# IFscaner.net
KiCad netlist of a schematic drawn in Altium Designer
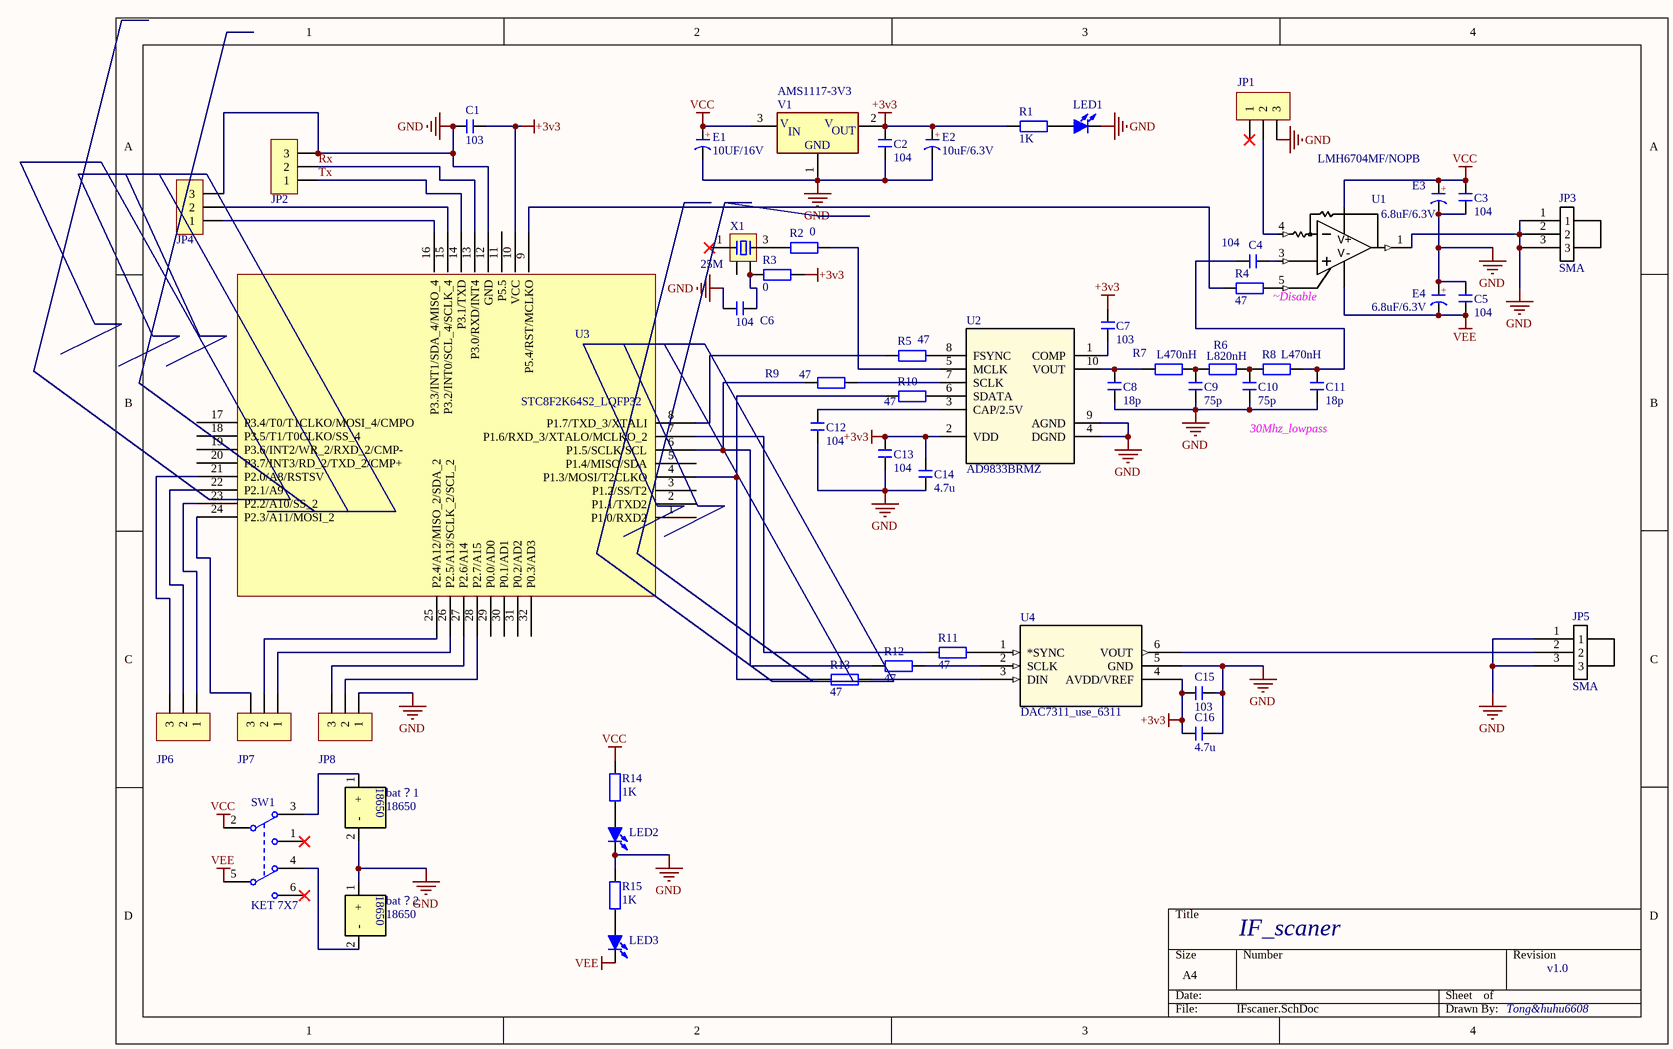
[diagram p0: IFscaner.SchDoc]

(export (version "E")
  (design (tool "Eeschema 10.0.6"))
  (components
    (comp (ref "bat？1") (value "18650") (footprint "18650base") (libsource (lib "InBoard") (part "18650")))
    (comp (ref "bat？2") (value "18650") (footprint "18650base") (libsource (lib "InBoard") (part "18650")))
    (comp (ref "C1")
      (value "103")
      (footprint "C 0603")
      (description "无极性贴片电容")
      (fields (field (name "版权归属") "源创客"))
      (libsource (lib "InBoard") (part "C"))
    )
    (comp (ref "C2")
      (value "104")
      (footprint "C 0603")
      (description "无极性贴片电容")
      (fields (field (name "版权归属") "源创客"))
      (libsource (lib "InBoard") (part "C"))
    )
    (comp (ref "C3")
      (value "104")
      (footprint "C 0603")
      (description "无极性贴片电容")
      (fields (field (name "版权归属") "源创客"))
      (libsource (lib "InBoard") (part "C"))
    )
    (comp (ref "C4")
      (value "104")
      (footprint "C 0603")
      (description "无极性贴片电容")
      (fields (field (name "版权归属") "源创客"))
      (libsource (lib "InBoard") (part "C"))
    )
    (comp (ref "C5")
      (value "104")
      (footprint "C 0603")
      (description "无极性贴片电容")
      (fields (field (name "版权归属") "源创客"))
      (libsource (lib "InBoard") (part "C"))
    )
    (comp (ref "C6")
      (value "104")
      (footprint "C 0603")
      (description "无极性贴片电容")
      (fields (field (name "版权归属") "源创客"))
      (libsource (lib "InBoard") (part "C"))
    )
    (comp (ref "C7")
      (value "103")
      (footprint "C 0603")
      (description "无极性贴片电容")
      (fields (field (name "版权归属") "源创客"))
      (libsource (lib "InBoard") (part "C"))
    )
    (comp (ref "C8")
      (value "18p")
      (footprint "C 0603")
      (description "无极性贴片电容")
      (fields (field (name "版权归属") "源创客"))
      (libsource (lib "InBoard") (part "C"))
    )
    (comp (ref "C9")
      (value "75p")
      (footprint "C 0603")
      (description "无极性贴片电容")
      (fields (field (name "版权归属") "源创客"))
      (libsource (lib "InBoard") (part "C"))
    )
    (comp (ref "C10")
      (value "75p")
      (footprint "C 0603")
      (description "无极性贴片电容")
      (fields (field (name "版权归属") "源创客"))
      (libsource (lib "InBoard") (part "C"))
    )
    (comp (ref "C11")
      (value "18p")
      (footprint "C 0603")
      (description "无极性贴片电容")
      (fields (field (name "版权归属") "源创客"))
      (libsource (lib "InBoard") (part "C"))
    )
    (comp (ref "C12")
      (value "104")
      (footprint "C 0603")
      (description "无极性贴片电容")
      (fields (field (name "版权归属") "源创客"))
      (libsource (lib "InBoard") (part "C"))
    )
    (comp (ref "C13")
      (value "104")
      (footprint "C 0603")
      (description "无极性贴片电容")
      (fields (field (name "版权归属") "源创客"))
      (libsource (lib "InBoard") (part "C"))
    )
    (comp (ref "C14")
      (value "4.7u")
      (footprint "C 0603")
      (description "无极性贴片电容")
      (fields (field (name "版权归属") "源创客"))
      (libsource (lib "InBoard") (part "C"))
    )
    (comp (ref "C15")
      (value "103")
      (footprint "C 0603")
      (description "无极性贴片电容")
      (fields (field (name "版权归属") "源创客"))
      (libsource (lib "InBoard") (part "C"))
    )
    (comp (ref "C16")
      (value "4.7u")
      (footprint "C 0603")
      (description "无极性贴片电容")
      (fields (field (name "版权归属") "源创客"))
      (libsource (lib "InBoard") (part "C"))
    )
    (comp (ref "E1")
      (value "10UF/16V")
      (footprint "CAP 5.0*10*20")
      (description "直插电解电容")
      (fields (field (name "版权归属") "源创客"))
      (libsource (lib "InBoard") (part "C-CAP"))
    )
    (comp (ref "E2")
      (value "10uF/6.3V")
      (footprint "CD B(3528)")
      (description "贴片钽电容")
      (fields (field (name "版权归属") "源创客"))
      (libsource (lib "InBoard") (part "C-CD"))
    )
    (comp (ref "E3")
      (value "6.8uF/6.3V")
      (footprint "CD B(3528)")
      (description "贴片钽电容")
      (fields (field (name "版权归属") "源创客"))
      (libsource (lib "InBoard") (part "C-CD"))
    )
    (comp (ref "E4")
      (value "6.8uF/6.3V")
      (footprint "CD B(3528)")
      (description "贴片钽电容")
      (fields (field (name "版权归属") "源创客"))
      (libsource (lib "InBoard") (part "C-CD"))
    )
    (comp (ref "JP1")
      (value "HDR-1X3")
      (footprint "HDR-1X3")
      (description "3P接插件")
      (fields (field (name "版权归属") "源创客"))
      (libsource (lib "") (part "Header 3_1"))
    )
    (comp (ref "JP2")
      (value "HDR-1X3")
      (footprint "HDR-1X3")
      (description "3P接插件")
      (fields (field (name "版权归属") "源创客"))
      (libsource (lib "") (part "Header 3_2"))
    )
    (comp (ref "JP3") (value "SMA") (footprint "SMA_khd") (libsource (lib "InBoard") (part "sma")))
    (comp (ref "JP4")
      (value "HDR-1X3")
      (footprint "HDR-1X3")
      (description "3P接插件")
      (fields (field (name "版权归属") "源创客"))
      (libsource (lib "") (part "Header 3_2"))
    )
    (comp (ref "JP5") (value "SMA") (footprint "SMA_khd") (libsource (lib "InBoard") (part "sma")))
    (comp (ref "JP6")
      (value "HDR-1X3")
      (footprint "HDR-1X3")
      (description "3P接插件")
      (fields (field (name "版权归属") "源创客"))
      (libsource (lib "InBoard") (part "Header 3"))
    )
    (comp (ref "JP7")
      (value "HDR-1X3")
      (footprint "HDR-1X3")
      (description "3P接插件")
      (fields (field (name "版权归属") "源创客"))
      (libsource (lib "InBoard") (part "Header 3"))
    )
    (comp (ref "JP8")
      (value "HDR-1X3")
      (footprint "HDR-1X3")
      (description "3P接插件")
      (fields (field (name "版权归属") "源创客"))
      (libsource (lib "InBoard") (part "Header 3"))
    )
    (comp (ref "LED1")
      (value "~")
      (footprint "LED 0603B")
      (description "贴片LED")
      (libsource (lib "InBoard") (part "LED-SMD"))
    )
    (comp (ref "LED2")
      (value "~")
      (footprint "LED 0603B")
      (description "贴片LED")
      (libsource (lib "InBoard") (part "LED-SMD"))
    )
    (comp (ref "LED3")
      (value "~")
      (footprint "LED 0603B")
      (description "贴片LED")
      (libsource (lib "InBoard") (part "LED-SMD"))
    )
    (comp (ref "R1")
      (value "1K")
      (footprint "R 0603")
      (description "贴片电阻")
      (fields (field (name "版权归属") "源创客"))
      (libsource (lib "InBoard") (part "R"))
    )
    (comp (ref "R2")
      (value "0")
      (footprint "R 0603")
      (description "贴片电阻")
      (fields (field (name "版权归属") "源创客"))
      (libsource (lib "InBoard") (part "R"))
    )
    (comp (ref "R3")
      (value "0")
      (footprint "R 0603")
      (description "贴片电阻")
      (fields (field (name "版权归属") "源创客"))
      (libsource (lib "InBoard") (part "R"))
    )
    (comp (ref "R4")
      (value "47")
      (footprint "R 0603")
      (description "贴片电阻")
      (fields (field (name "版权归属") "源创客"))
      (libsource (lib "InBoard") (part "R"))
    )
    (comp (ref "R5")
      (value "47")
      (footprint "R 0603")
      (description "贴片电阻")
      (fields (field (name "版权归属") "源创客"))
      (libsource (lib "InBoard") (part "R"))
    )
    (comp (ref "R6")
      (value "L820nH")
      (footprint "R 0603")
      (description "贴片电阻")
      (fields (field (name "版权归属") "源创客"))
      (libsource (lib "InBoard") (part "R"))
    )
    (comp (ref "R7")
      (value "L470nH")
      (footprint "R 0603")
      (description "贴片电阻")
      (fields (field (name "版权归属") "源创客"))
      (libsource (lib "InBoard") (part "R"))
    )
    (comp (ref "R8")
      (value "L470nH")
      (footprint "R 0603")
      (description "贴片电阻")
      (fields (field (name "版权归属") "源创客"))
      (libsource (lib "InBoard") (part "R"))
    )
    (comp (ref "R9")
      (value "47")
      (footprint "R 0603")
      (description "贴片电阻")
      (fields (field (name "版权归属") "源创客"))
      (libsource (lib "InBoard") (part "R"))
    )
    (comp (ref "R10")
      (value "47")
      (footprint "R 0603")
      (description "贴片电阻")
      (fields (field (name "版权归属") "源创客"))
      (libsource (lib "InBoard") (part "R"))
    )
    (comp (ref "R11")
      (value "47")
      (footprint "R 0603")
      (description "贴片电阻")
      (fields (field (name "版权归属") "源创客"))
      (libsource (lib "InBoard") (part "R"))
    )
    (comp (ref "R12")
      (value "47")
      (footprint "R 0603")
      (description "贴片电阻")
      (fields (field (name "版权归属") "源创客"))
      (libsource (lib "InBoard") (part "R"))
    )
    (comp (ref "R13")
      (value "47")
      (footprint "R 0603")
      (description "贴片电阻")
      (fields (field (name "版权归属") "源创客"))
      (libsource (lib "InBoard") (part "R"))
    )
    (comp (ref "R14")
      (value "1K")
      (footprint "R 0603")
      (description "贴片电阻")
      (fields (field (name "版权归属") "源创客"))
      (libsource (lib "InBoard") (part "R"))
    )
    (comp (ref "R15")
      (value "1K")
      (footprint "R 0603")
      (description "贴片电阻")
      (fields (field (name "版权归属") "源创客"))
      (libsource (lib "InBoard") (part "R"))
    )
    (comp (ref "SW1")
      (value "KET 7X7")
      (footprint "KFT DIP-7X7")
      (description "7*7自锁开关")
      (fields (field (name "版权归属") "源创客"))
      (libsource (lib "InBoard") (part "KET 7X7"))
    )
    (comp (ref "U1")
      (value "LMH6704MF/NOPB")
      (footprint "SOT23-6L")
      (fields
        (field (name "PARTNUMBER") "LMH6704MF")
        (field (name "MANUFACTURER") "NationalSemiconductor")
        (field (name "COPYRIGHT") "Copyright (C) 2018 Accelerated Designs. All rights reserved")
        (field (name "PUBLISHER") "NationalSemiconductor")
      )
      (libsource (lib "InBoard") (part "LMH6704MF/NOPB"))
    )
    (comp (ref "U2")
      (value "AD9833BRMZ")
      (footprint "RM_10")
      (description "Imported")
      (libsource (lib "InBoard") (part "AD9833BRMZ"))
    )
    (comp (ref "U3")
      (value "STC8F2K64S2_LQFP32")
      (footprint "LQFP32")
      (libsource (lib "InBoard") (part "STC8F2K32S2_LQFP32"))
    )
    (comp (ref "U4")
      (value "DAC7311_use_6311")
      (footprint "DCK6")
      (description "Imported")
      (fields
        (field (name "MANUFACTURER") "Texas Instruments")
        (field (name "GENERIC_PART_NUMBER") "DAC7311")
      )
      (libsource (lib "InBoard") (part "DAC7311_DCK_6"))
    )
    (comp (ref "V1")
      (value "AMS1117-3V3")
      (footprint "SOT223")
      (description "三端稳压芯片")
      (libsource (lib "InBoard") (part "AMS1117"))
    )
    (comp (ref "X1")
      (value "25M")
      (footprint "XTAL-3225")
      (description "4脚晶振")
      (libsource (lib "InBoard") (part "XTAL-4"))
    )
  )
  (nets
    (net (code "1") (name "+3v3") (class "Default")
      (node (ref "C1") (pin "2") (pinfunction "2_2") (pintype "passive"))
      (node (ref "C13") (pin "1") (pinfunction "1_1") (pintype "passive"))
      (node (ref "C14") (pin "1") (pinfunction "1_1") (pintype "passive"))
      (node (ref "C15") (pin "2") (pinfunction "2_2") (pintype "passive"))
      (node (ref "C16") (pin "2") (pinfunction "2_2") (pintype "passive"))
      (node (ref "C2") (pin "2") (pinfunction "2_2") (pintype "passive"))
      (node (ref "C7") (pin "2") (pinfunction "2_2") (pintype "passive"))
      (node (ref "E2") (pin "1") (pinfunction "A_1") (pintype "passive"))
      (node (ref "R1") (pin "2") (pinfunction "2_2") (pintype "passive"))
      (node (ref "R3") (pin "2") (pinfunction "2_2") (pintype "passive"))
      (node (ref "U2") (pin "2") (pinfunction "VDD_2") (pintype "power_in"))
      (node (ref "U3") (pin "10") (pinfunction "VCC_10") (pintype "passive"))
      (node (ref "U4") (pin "4") (pinfunction "AVDD/VREF_4") (pintype "power_in"))
      (node (ref "V1") (pin "2") (pinfunction "VOUT_2") (pintype "passive"))
    )
    (net (code "2") (name "/Rx") (class "Default")
      (node (ref "JP2") (pin "2") (pinfunction "2_2") (pintype "passive"))
      (node (ref "U3") (pin "13") (pinfunction "P3.0/RXD/INT4_13") (pintype "passive"))
    )
    (net (code "3") (name "/Tx") (class "Default")
      (node (ref "JP2") (pin "1") (pinfunction "1_1") (pintype "passive"))
      (node (ref "U3") (pin "14") (pinfunction "P3.1/TXD_14") (pintype "passive"))
    )
    (net (code "4") (name "GND") (class "Default")
      (node (ref "C1") (pin "1") (pinfunction "1_1") (pintype "passive"))
      (node (ref "C10") (pin "2") (pinfunction "2_2") (pintype "passive"))
      (node (ref "C11") (pin "2") (pinfunction "2_2") (pintype "passive"))
      (node (ref "C12") (pin "2") (pinfunction "2_2") (pintype "passive"))
      (node (ref "C13") (pin "2") (pinfunction "2_2") (pintype "passive"))
      (node (ref "C14") (pin "2") (pinfunction "2_2") (pintype "passive"))
      (node (ref "C15") (pin "1") (pinfunction "1_1") (pintype "passive"))
      (node (ref "C16") (pin "1") (pinfunction "1_1") (pintype "passive"))
      (node (ref "C2") (pin "1") (pinfunction "1_1") (pintype "passive"))
      (node (ref "C3") (pin "1") (pinfunction "1_1") (pintype "passive"))
      (node (ref "C5") (pin "2") (pinfunction "2_2") (pintype "passive"))
      (node (ref "C6") (pin "1") (pinfunction "1_1") (pintype "passive"))
      (node (ref "C8") (pin "2") (pinfunction "2_2") (pintype "passive"))
      (node (ref "C9") (pin "2") (pinfunction "2_2") (pintype "passive"))
      (node (ref "E1") (pin "2") (pinfunction "K_2") (pintype "passive"))
      (node (ref "E2") (pin "2") (pinfunction "K_2") (pintype "passive"))
      (node (ref "E3") (pin "2") (pinfunction "K_2") (pintype "passive"))
      (node (ref "E4") (pin "1") (pinfunction "A_1") (pintype "passive"))
      (node (ref "JP1") (pin "3") (pinfunction "3_3") (pintype "passive"))
      (node (ref "JP2") (pin "3") (pinfunction "3_3") (pintype "passive"))
      (node (ref "JP3") (pin "1") (pinfunction "1_1") (pintype "passive"))
      (node (ref "JP3") (pin "2") (pinfunction "2_2") (pintype "passive"))
      (node (ref "JP3") (pin "3") (pinfunction "3_3") (pintype "passive"))
      (node (ref "JP4") (pin "3") (pinfunction "3_3") (pintype "passive"))
      (node (ref "JP5") (pin "1") (pinfunction "1_1") (pintype "passive"))
      (node (ref "JP5") (pin "3") (pinfunction "3_3") (pintype "passive"))
      (node (ref "JP8") (pin "1") (pinfunction "1_1") (pintype "passive"))
      (node (ref "LED1") (pin "2") (pinfunction "K_2") (pintype "passive"))
      (node (ref "LED2") (pin "2") (pinfunction "K_2") (pintype "passive"))
      (node (ref "R15") (pin "2") (pinfunction "2_2") (pintype "passive"))
      (node (ref "U1") (pin "1") (pinfunction "A_OUT_1") (pintype "output"))
      (node (ref "U2") (pin "4") (pinfunction "DGND_4") (pintype "passive"))
      (node (ref "U2") (pin "9") (pinfunction "AGND_9") (pintype "passive"))
      (node (ref "U3") (pin "12") (pinfunction "GND_12") (pintype "passive"))
      (node (ref "U4") (pin "5") (pinfunction "GND_5") (pintype "power_in"))
      (node (ref "V1") (pin "1") (pinfunction "GND_1") (pintype "passive"))
      (node (ref "bat？1") (pin "2") (pinfunction "-_2") (pintype "passive"))
      (node (ref "bat？2") (pin "1") (pinfunction "+_1") (pintype "passive"))
    )
    (net (code "5") (name "Net-(C6-Pad2)") (class "Default")
      (node (ref "C6") (pin "2") (pinfunction "2_2") (pintype "passive"))
      (node (ref "R3") (pin "1") (pinfunction "1_1") (pintype "passive"))
      (node (ref "X1") (pin "4") (pinfunction "4_4") (pintype "passive"))
    )
    (net (code "6") (name "Net-(C9-Pad1)") (class "Default")
      (node (ref "C9") (pin "1") (pinfunction "1_1") (pintype "passive"))
      (node (ref "R6") (pin "1") (pinfunction "1_1") (pintype "passive"))
      (node (ref "R7") (pin "2") (pinfunction "2_2") (pintype "passive"))
    )
    (net (code "7") (name "Net-(C10-Pad1)") (class "Default")
      (node (ref "C10") (pin "1") (pinfunction "1_1") (pintype "passive"))
      (node (ref "R6") (pin "2") (pinfunction "2_2") (pintype "passive"))
      (node (ref "R8") (pin "1") (pinfunction "1_1") (pintype "passive"))
    )
    (net (code "8") (name "Net-(C11-Pad1)") (class "Default")
      (node (ref "C11") (pin "1") (pinfunction "1_1") (pintype "passive"))
      (node (ref "C4") (pin "1") (pinfunction "1_1") (pintype "passive"))
      (node (ref "R8") (pin "2") (pinfunction "2_2") (pintype "passive"))
    )
    (net (code "9") (name "Net-(LED1-A)") (class "Default")
      (node (ref "LED1") (pin "1") (pinfunction "A_1") (pintype "passive"))
      (node (ref "R1") (pin "1") (pinfunction "1_1") (pintype "passive"))
    )
    (net (code "10") (name "Net-(LED2-A)") (class "Default")
      (node (ref "LED2") (pin "1") (pinfunction "A_1") (pintype "passive"))
      (node (ref "R14") (pin "1") (pinfunction "1_1") (pintype "passive"))
    )
    (net (code "11") (name "Net-(LED3-A)") (class "Default")
      (node (ref "LED3") (pin "1") (pinfunction "A_1") (pintype "passive"))
      (node (ref "R15") (pin "1") (pinfunction "1_1") (pintype "passive"))
    )
    (net (code "12") (name "Net-(R2-Pad1)") (class "Default")
      (node (ref "R2") (pin "1") (pinfunction "1_1") (pintype "passive"))
      (node (ref "X1") (pin "3") (pinfunction "3_3") (pintype "passive"))
    )
    (net (code "13") (name "Net-(SW1-NO1)") (class "Default")
      (node (ref "SW1") (pin "3") (pinfunction "NO1_3") (pintype "passive"))
      (node (ref "bat？1") (pin "1") (pinfunction "+_1") (pintype "passive"))
    )
    (net (code "14") (name "Net-(SW1-NO2)") (class "Default")
      (node (ref "SW1") (pin "4") (pinfunction "NO2_4") (pintype "passive"))
      (node (ref "bat？2") (pin "2") (pinfunction "-_2") (pintype "passive"))
    )
    (net (code "15") (name "Net-(U1-DIS)") (class "Default")
      (node (ref "R4") (pin "2") (pinfunction "2_2") (pintype "passive"))
      (node (ref "U1") (pin "5") (pinfunction "DIS_5") (pintype "input"))
    )
    (net (code "16") (name "Net-(U1-IN+)") (class "Default")
      (node (ref "C4") (pin "2") (pinfunction "2_2") (pintype "passive"))
      (node (ref "U1") (pin "3") (pinfunction "IN+_3") (pintype "input"))
    )
    (net (code "17") (name "Net-(U1-IN-)") (class "Default")
      (node (ref "JP1") (pin "2") (pinfunction "2_2") (pintype "passive"))
      (node (ref "U1") (pin "4") (pinfunction "IN-_4") (pintype "input"))
    )
    (net (code "18") (name "Net-(U2-CAP{slash}2.5V)") (class "Default")
      (node (ref "C12") (pin "1") (pinfunction "1_1") (pintype "passive"))
      (node (ref "U2") (pin "3") (pinfunction "CAP/2.5V_3") (pintype "power_in"))
    )
    (net (code "19") (name "Net-(U2-COMP)") (class "Default")
      (node (ref "C7") (pin "1") (pinfunction "1_1") (pintype "passive"))
      (node (ref "U2") (pin "1") (pinfunction "COMP_1") (pintype "passive"))
    )
    (net (code "20") (name "Net-(U2-FSYNC)") (class "Default")
      (node (ref "R5") (pin "2") (pinfunction "2_2") (pintype "passive"))
      (node (ref "U2") (pin "8") (pinfunction "FSYNC_8") (pintype "passive"))
    )
    (net (code "21") (name "Net-(U2-MCLK)") (class "Default")
      (node (ref "R2") (pin "2") (pinfunction "2_2") (pintype "passive"))
      (node (ref "U2") (pin "5") (pinfunction "MCLK_5") (pintype "passive"))
    )
    (net (code "22") (name "Net-(U2-SCLK)") (class "Default")
      (node (ref "R9") (pin "2") (pinfunction "2_2") (pintype "passive"))
      (node (ref "U2") (pin "7") (pinfunction "SCLK_7") (pintype "passive"))
    )
    (net (code "23") (name "Net-(U2-SDATA)") (class "Default")
      (node (ref "R10") (pin "2") (pinfunction "2_2") (pintype "passive"))
      (node (ref "U2") (pin "6") (pinfunction "SDATA_6") (pintype "passive"))
    )
    (net (code "24") (name "Net-(U2-VOUT)") (class "Default")
      (node (ref "C8") (pin "1") (pinfunction "1_1") (pintype "passive"))
      (node (ref "R7") (pin "1") (pinfunction "1_1") (pintype "passive"))
      (node (ref "U2") (pin "10") (pinfunction "VOUT_10") (pintype "passive"))
    )
    (net (code "25") (name "Net-(U3-P1.3{slash}MOSI{slash}T2CLKO)") (class "Default")
      (node (ref "R10") (pin "1") (pinfunction "1_1") (pintype "passive"))
      (node (ref "R13") (pin "1") (pinfunction "1_1") (pintype "passive"))
      (node (ref "U3") (pin "4") (pinfunction "P1.3/MOSI/T2CLKO_4") (pintype "passive"))
    )
    (net (code "26") (name "Net-(U3-P1.5{slash}SCLK{slash}SCL)") (class "Default")
      (node (ref "R12") (pin "1") (pinfunction "1_1") (pintype "passive"))
      (node (ref "R9") (pin "1") (pinfunction "1_1") (pintype "passive"))
      (node (ref "U3") (pin "6") (pinfunction "P1.5/SCLK/SCL_6") (pintype "passive"))
    )
    (net (code "27") (name "Net-(U3-P1.6{slash}RXD_3{slash}XTALO{slash}MCLKO_2)") (class "Default")
      (node (ref "R11") (pin "1") (pinfunction "1_1") (pintype "passive"))
      (node (ref "U3") (pin "7") (pinfunction "P1.6/RXD_3/XTALO/MCLKO_2_7") (pintype "passive"))
    )
    (net (code "28") (name "Net-(U3-P1.7{slash}TXD_3{slash}XTALI)") (class "Default")
      (node (ref "R5") (pin "1") (pinfunction "1_1") (pintype "passive"))
      (node (ref "U3") (pin "8") (pinfunction "P1.7/TXD_3/XTALI_8") (pintype "passive"))
    )
    (net (code "29") (name "Net-(U3-P2.0{slash}A8{slash}RSTSV)") (class "Default")
      (node (ref "JP6") (pin "3") (pinfunction "3_3") (pintype "passive"))
      (node (ref "U3") (pin "21") (pinfunction "P2.0/A8/RSTSV_21") (pintype "passive"))
    )
    (net (code "30") (name "Net-(U3-P2.1{slash}A9)") (class "Default")
      (node (ref "JP6") (pin "2") (pinfunction "2_2") (pintype "passive"))
      (node (ref "U3") (pin "22") (pinfunction "P2.1/A9_22") (pintype "passive"))
    )
    (net (code "31") (name "Net-(U3-P2.2{slash}A10{slash}SS_2)") (class "Default")
      (node (ref "JP6") (pin "1") (pinfunction "1_1") (pintype "passive"))
      (node (ref "U3") (pin "23") (pinfunction "P2.2/A10/SS_2_23") (pintype "passive"))
    )
    (net (code "32") (name "Net-(U3-P2.3{slash}A11{slash}MOSI_2)") (class "Default")
      (node (ref "JP7") (pin "3") (pinfunction "3_3") (pintype "passive"))
      (node (ref "U3") (pin "24") (pinfunction "P2.3/A11/MOSI_2_24") (pintype "passive"))
    )
    (net (code "33") (name "Net-(U3-P2.4{slash}A12{slash}MISO_2{slash}SDA_2)") (class "Default")
      (node (ref "JP7") (pin "2") (pinfunction "2_2") (pintype "passive"))
      (node (ref "U3") (pin "25") (pinfunction "P2.4/A12/MISO_2/SDA_2_25") (pintype "passive"))
    )
    (net (code "34") (name "Net-(U3-P2.5{slash}A13{slash}SCLK_2{slash}SCL_2)") (class "Default")
      (node (ref "JP7") (pin "1") (pinfunction "1_1") (pintype "passive"))
      (node (ref "U3") (pin "26") (pinfunction "P2.5/A13/SCLK_2/SCL_2_26") (pintype "passive"))
    )
    (net (code "35") (name "Net-(U3-P2.6{slash}A14)") (class "Default")
      (node (ref "JP8") (pin "3") (pinfunction "3_3") (pintype "passive"))
      (node (ref "U3") (pin "27") (pinfunction "P2.6/A14_27") (pintype "passive"))
    )
    (net (code "36") (name "Net-(U3-P2.7{slash}A15)") (class "Default")
      (node (ref "JP8") (pin "2") (pinfunction "2_2") (pintype "passive"))
      (node (ref "U3") (pin "28") (pinfunction "P2.7/A15_28") (pintype "passive"))
    )
    (net (code "37") (name "Net-(U3-P3.2{slash}INT0{slash}SCL_4{slash}SCLK_4)") (class "Default")
      (node (ref "JP4") (pin "2") (pinfunction "2_2") (pintype "passive"))
      (node (ref "U3") (pin "15") (pinfunction "P3.2/INT0/SCL_4/SCLK_4_15") (pintype "passive"))
    )
    (net (code "38") (name "Net-(U3-P3.3{slash}INT1{slash}SDA_4{slash}MISO_4)") (class "Default")
      (node (ref "JP4") (pin "1") (pinfunction "1_1") (pintype "passive"))
      (node (ref "U3") (pin "16") (pinfunction "P3.3/INT1/SDA_4/MISO_4_16") (pintype "passive"))
    )
    (net (code "39") (name "Net-(U3-P5.4{slash}RST{slash}MCLKO)") (class "Default")
      (node (ref "R4") (pin "1") (pinfunction "1_1") (pintype "passive"))
      (node (ref "U3") (pin "9") (pinfunction "P5.4/RST/MCLKO_9") (pintype "passive"))
    )
    (net (code "40") (name "Net-(U4-*SYNC)") (class "Default")
      (node (ref "R11") (pin "2") (pinfunction "2_2") (pintype "passive"))
      (node (ref "U4") (pin "1") (pinfunction "*SYNC_1") (pintype "input"))
    )
    (net (code "41") (name "Net-(U4-DIN)") (class "Default")
      (node (ref "R13") (pin "2") (pinfunction "2_2") (pintype "passive"))
      (node (ref "U4") (pin "3") (pinfunction "DIN_3") (pintype "input"))
    )
    (net (code "42") (name "Net-(U4-SCLK)") (class "Default")
      (node (ref "R12") (pin "2") (pinfunction "2_2") (pintype "passive"))
      (node (ref "U4") (pin "2") (pinfunction "SCLK_2") (pintype "input"))
    )
    (net (code "43") (name "Net-(U4-VOUT)") (class "Default")
      (node (ref "JP5") (pin "2") (pinfunction "2_2") (pintype "passive"))
      (node (ref "U4") (pin "6") (pinfunction "VOUT_6") (pintype "output"))
    )
    (net (code "44") (name "VCC") (class "Default")
      (node (ref "C3") (pin "2") (pinfunction "2_2") (pintype "passive"))
      (node (ref "E1") (pin "1") (pinfunction "A_1") (pintype "passive"))
      (node (ref "E3") (pin "1") (pinfunction "A_1") (pintype "passive"))
      (node (ref "R14") (pin "2") (pinfunction "2_2") (pintype "passive"))
      (node (ref "SW1") (pin "2") (pinfunction "COM2_2") (pintype "passive"))
      (node (ref "V1") (pin "3") (pinfunction "VIN_3") (pintype "passive"))
    )
    (net (code "45") (name "VEE") (class "Default")
      (node (ref "C5") (pin "1") (pinfunction "1_1") (pintype "passive"))
      (node (ref "E4") (pin "2") (pinfunction "K_2") (pintype "passive"))
      (node (ref "LED3") (pin "2") (pinfunction "K_2") (pintype "passive"))
      (node (ref "SW1") (pin "5") (pinfunction "COM2_5") (pintype "passive"))
    )
    (net (code "46") (name "unconnected-(JP1-Pad1)") (class "Default")
      (node (ref "JP1") (pin "1") (pinfunction "1_1") (pintype "passive+no_connect"))
    )
    (net (code "47") (name "unconnected-(SW1-NC1-Pad1)") (class "Default")
      (node (ref "SW1") (pin "1") (pinfunction "NC1_1") (pintype "passive+no_connect"))
    )
    (net (code "48") (name "unconnected-(SW1-NC2-Pad6)") (class "Default")
      (node (ref "SW1") (pin "6") (pinfunction "NC2_6") (pintype "passive+no_connect"))
    )
    (net (code "49") (name "unconnected-(U3-P0.0{slash}AD0-Pad29)") (class "Default")
      (node (ref "U3") (pin "29") (pinfunction "P0.0/AD0_29") (pintype "passive"))
    )
    (net (code "50") (name "unconnected-(U3-P0.1{slash}AD1-Pad30)") (class "Default")
      (node (ref "U3") (pin "30") (pinfunction "P0.1/AD1_30") (pintype "passive"))
    )
    (net (code "51") (name "unconnected-(U3-P0.2{slash}AD2-Pad31)") (class "Default")
      (node (ref "U3") (pin "31") (pinfunction "P0.2/AD2_31") (pintype "passive"))
    )
    (net (code "52") (name "unconnected-(U3-P0.3{slash}AD3-Pad32)") (class "Default")
      (node (ref "U3") (pin "32") (pinfunction "P0.3/AD3_32") (pintype "passive"))
    )
    (net (code "53") (name "unconnected-(U3-P1.0{slash}RXD2-Pad1)") (class "Default")
      (node (ref "U3") (pin "1") (pinfunction "P1.0/RXD2_1") (pintype "passive"))
    )
    (net (code "54") (name "unconnected-(U3-P1.1{slash}TXD2-Pad2)") (class "Default")
      (node (ref "U3") (pin "2") (pinfunction "P1.1/TXD2_2") (pintype "passive"))
    )
    (net (code "55") (name "unconnected-(U3-P1.2{slash}SS{slash}T2-Pad3)") (class "Default")
      (node (ref "U3") (pin "3") (pinfunction "P1.2/SS/T2_3") (pintype "passive"))
    )
    (net (code "56") (name "unconnected-(U3-P1.4{slash}MISO{slash}SDA-Pad5)") (class "Default")
      (node (ref "U3") (pin "5") (pinfunction "P1.4/MISO/SDA_5") (pintype "passive"))
    )
    (net (code "57") (name "unconnected-(U3-P3.4{slash}T0{slash}T1CLKO{slash}MOSI_4{slash}CMPO-Pad17)") (class "Default")
      (node (ref "U3") (pin "17") (pinfunction "P3.4/T0/T1CLKO/MOSI_4/CMPO_17") (pintype "passive"))
    )
    (net (code "58") (name "unconnected-(U3-P3.5{slash}T1{slash}T0CLKO{slash}SS_4-Pad18)") (class "Default")
      (node (ref "U3") (pin "18") (pinfunction "P3.5/T1/T0CLKO/SS_4_18") (pintype "passive"))
    )
    (net (code "59") (name "unconnected-(U3-P3.6{slash}INT2{slash}WR_2{slash}RXD_2{slash}CMP--Pad19)") (class "Default")
      (node (ref "U3") (pin "19") (pinfunction "P3.6/INT2/WR_2/RXD_2/CMP-_19") (pintype "passive"))
    )
    (net (code "60") (name "unconnected-(U3-P3.7{slash}INT3{slash}RD_2{slash}TXD_2{slash}CMP+-Pad20)") (class "Default")
      (node (ref "U3") (pin "20") (pinfunction "P3.7/INT3/RD_2/TXD_2/CMP+_20") (pintype "passive"))
    )
    (net (code "61") (name "unconnected-(U3-P5.5-Pad11)") (class "Default")
      (node (ref "U3") (pin "11") (pinfunction "P5.5_11") (pintype "passive"))
    )
    (net (code "62") (name "unconnected-(X1-Pad1)") (class "Default")
      (node (ref "X1") (pin "1") (pinfunction "1_1") (pintype "passive+no_connect"))
    )
    (net (code "63") (name "unconnected-(X1-Pad2)") (class "Default")
      (node (ref "X1") (pin "2") (pinfunction "2_2") (pintype "passive"))
    )
  )
)
